# Control_and_gauge.net
KiCad netlist of a schematic drawn in Altium Designer
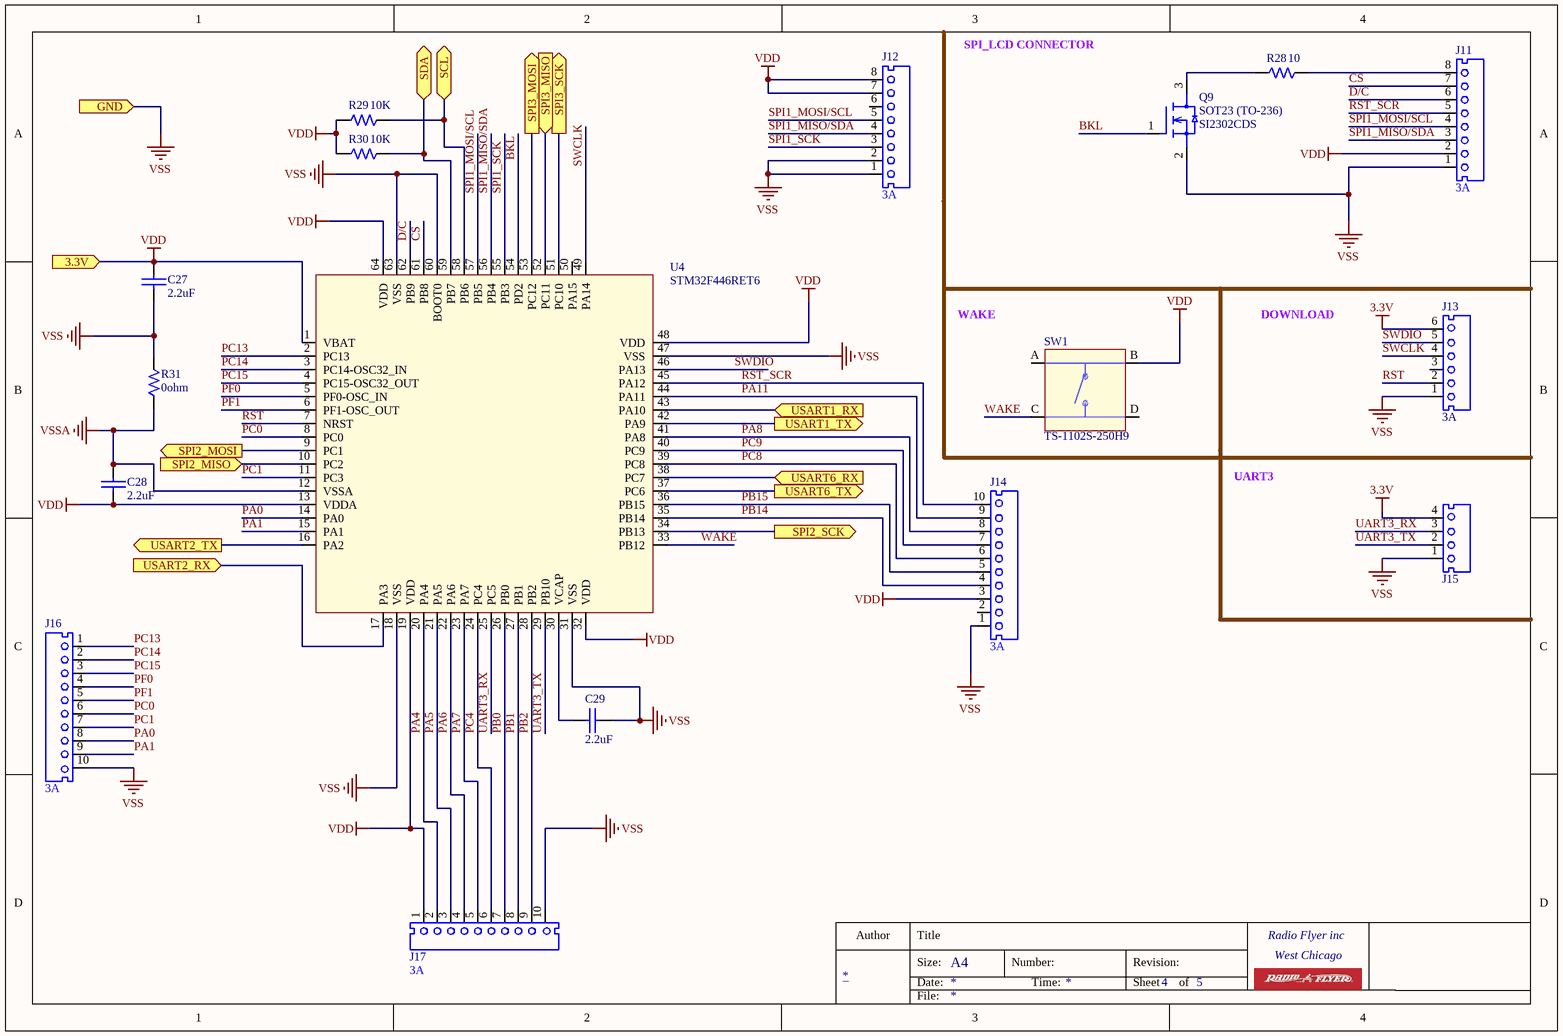
[diagram p0: Control and gauge.SchDoc]

(export (version "E")
  (design (tool "Eeschema 10.0.6"))
  (components
    (comp (ref "C27")
      (value "2.2uF")
      (footprint "CAPC0603-RW")
      (description "CAP X7R .01UF 16V +-10% 0603 WALSIN L")
      (fields
        (field (name "MFG") "WALSIN")
        (field (name "TOLERANCE") "10%")
        (field (name "CREATE_NAME") "Nathan")
      )
      (libsource (lib "P-Capacitors") (part "CAP0603 0.01uF 16V 10%_X7R_WALSIN"))
    )
    (comp (ref "C28")
      (value "2.2uF")
      (footprint "CAPC0603-RW")
      (description "CAP X7R .01UF 16V +-10% 0603 WALSIN L")
      (fields
        (field (name "MFG") "WALSIN")
        (field (name "TOLERANCE") "10%")
        (field (name "CREATE_NAME") "Nathan")
      )
      (libsource (lib "P-Capacitors") (part "CAP0603 0.01uF 16V 10%_X7R_WALSIN"))
    )
    (comp (ref "C29")
      (value "2.2uF")
      (footprint "CAPC0603-RW")
      (description "CAP X7R .01UF 16V +-10% 0603 WALSIN L")
      (fields
        (field (name "MFG") "WALSIN")
        (field (name "TOLERANCE") "10%")
        (field (name "CREATE_NAME") "Nathan")
      )
      (libsource (lib "P-Capacitors") (part "CAP0603 0.01uF 16V 10%_X7R_WALSIN"))
    )
    (comp (ref "J11")
      (value "T690300135100")
      (footprint "CONN 8P PH=2.5 ST TJC3-8A-CS")
      (description "CONN 8PIN P2.5 M\\180 TJC3-8A-CS K")
      (fields
        (field (name "MFG") "JINJIA")
        (field (name "MFG PART") "TJC3-8A-CS")
        (field (name "CURRENT") "3A")
        (field (name "CREATE_NAME") "Nathan")
      )
      (libsource (lib "") (part "CONN 8P PH=2.5 ST TJC3-8A-CS_1"))
    )
    (comp (ref "J12")
      (value "T690300135100")
      (footprint "CONN 8P PH=2.5 ST TJC3-8A-CS")
      (description "CONN 8PIN P2.5 M\\180 TJC3-8A-CS K")
      (fields
        (field (name "MFG") "JINJIA")
        (field (name "MFG PART") "TJC3-8A-CS")
        (field (name "CURRENT") "3A")
        (field (name "CREATE_NAME") "Nathan")
      )
      (libsource (lib "C-Connector") (part "CONN 8P PH=2.5 ST TJC3-8A-CS"))
    )
    (comp (ref "J13")
      (value "CCN250000-0106")
      (footprint "CONN 6P PH=2.5mm B6B-XH-A")
      (description "GP CONNECTOR B6B-XH-A 6 PIN")
      (fields (field (name "CURRENT") "3A"))
      (libsource (lib "C-Connector") (part "CONN 6P PH=2.5mm B6B-XH-A"))
    )
    (comp (ref "J14")
      (value "T690300163300")
      (footprint "CONN 10P PH=2.5 ST TJC3-10A-CS")
      (description "CONN 10PIN P2.5 M\\180 TJC3-10A-CS K")
      (fields
        (field (name "MFG") "JINJIA")
        (field (name "MFG PART") "TJC3-10A-CS")
        (field (name "CURRENT") "3A")
        (field (name "CREATE_NAME") "Nathan")
      )
      (libsource (lib "C-Connector") (part "CONN 10P PH=2.5 ST TJC3-10A-CS"))
    )
    (comp (ref "J15")
      (value "T690300164400")
      (footprint "CONN 4P PH=2.5mm 440052-4")
      (description "GP CONNECTOR B4B-XH-A 4 PIN")
      (fields
        (field (name "MFG") "TE")
        (field (name "MFG PART") "440052-4")
        (field (name "CREATE_NAME") "Nathan")
      )
      (libsource (lib "C-Connector") (part "CONN 4P PH=2.5mm 440052-4_TE"))
    )
    (comp (ref "J16")
      (value "T690300163300")
      (footprint "CONN 10P PH=2.5 ST TJC3-10A-CS")
      (description "CONN 10PIN P2.5 M\\180 TJC3-10A-CS K")
      (fields
        (field (name "MFG") "JINJIA")
        (field (name "MFG PART") "TJC3-10A-CS")
        (field (name "CURRENT") "3A")
        (field (name "CREATE_NAME") "Nathan")
      )
      (libsource (lib "C-Connector") (part "CONN 10P PH=2.5 ST TJC3-10A-CS"))
    )
    (comp (ref "J17")
      (value "T690300163300")
      (footprint "CONN 10P PH=2.5 ST TJC3-10A-CS")
      (description "CONN 10PIN P2.5 M\\180 TJC3-10A-CS K")
      (fields
        (field (name "MFG") "JINJIA")
        (field (name "MFG PART") "TJC3-10A-CS")
        (field (name "CURRENT") "3A")
        (field (name "CREATE_NAME") "Nathan")
      )
      (libsource (lib "C-Connector") (part "CONN 10P PH=2.5 ST TJC3-10A-CS"))
    )
    (comp (ref "Q9")
      (value "SI2302CDS")
      (footprint "SOT23-132-RW")
      (description "NMOS FET-Si2302CDS")
      (fields
        (field (name "MFG") "VISHAY")
        (field (name "PACKAGE") "SOT23 (TO-236)")
        (field (name "MFG PART") "SI2302CDS")
        (field (name "CREATE_NAME") "Nathan")
      )
      (libsource (lib "R-Semiconductors") (part "SI2302CDS"))
    )
    (comp (ref "R28")
      (value "10")
      (footprint "0603-RW")
      (description "CHIP 976 OHM 100PPM +-1% 0603 WALS L")
      (fields (field (name "POWER") "0.1W") (field (name "MFG") "WALSIN") (field (name "CREATE_NAME") "Tom"))
      (libsource (lib "Q-Resistors") (part "RES0603 1/10W +-1% 976 OHM 100PPM"))
    )
    (comp (ref "R29")
      (value "10K")
      (footprint "0603-RW")
      (description "CHIP 976 OHM 100PPM +-1% 0603 WALS L")
      (fields (field (name "POWER") "0.1W") (field (name "MFG") "WALSIN") (field (name "CREATE_NAME") "Tom"))
      (libsource (lib "Q-Resistors") (part "RES0603 1/10W +-1% 976 OHM 100PPM"))
    )
    (comp (ref "R30")
      (value "10K")
      (footprint "0603-RW")
      (description "CHIP 976 OHM 100PPM +-1% 0603 WALS L")
      (fields (field (name "POWER") "0.1W") (field (name "MFG") "WALSIN") (field (name "CREATE_NAME") "Tom"))
      (libsource (lib "Q-Resistors") (part "RES0603 1/10W +-1% 976 OHM 100PPM"))
    )
    (comp (ref "R31")
      (value "0ohm")
      (footprint "0603-RW")
      (description "CHIP 976 OHM 100PPM +-1% 0603 WALS L")
      (fields (field (name "POWER") "0.1W") (field (name "MFG") "WALSIN") (field (name "CREATE_NAME") "Tom"))
      (libsource (lib "Q-Resistors") (part "RES0603 1/10W +-1% 976 OHM 100PPM"))
    )
    (comp (ref "SW1")
      (value "T670200014500")
      (footprint "TACT SW TS-1102S-250H9")
      (description "TACT SW TS-1102S-250H9 JINGJU K")
      (fields
        (field (name "MFG") "JINGJU")
        (field (name "VOLTAGE") "12V")
        (field (name "MFG PART") "TS-1102S-250H9")
        (field (name "CREATE_NAME") "Nathan")
      )
      (libsource (lib "M-Controls") (part "TACT SW TS-1102S-250H9"))
    )
    (comp (ref "U4")
      (value "T610300097225")
      (footprint "QFP50P1200X1200X160-64N")
      (description "MCU STM32F030RCT6TR LQFP64 ST K")
      (fields
        (field (name "MFG") "ST     (STM意法半導體)")
        (field (name "MFG PART") "STM32F446RET6")
        (field (name "CREATE_NAME") "Nathan")
      )
      (libsource (lib "R-Semiconductors") (part "STM32F030RCT6TR"))
    )
  )
  (nets
    (net (code "1") (name "/BKL") (class "Default")
      (node (ref "Q9") (pin "1") (pinfunction "G_1") (pintype "passive"))
      (node (ref "U4") (pin "54") (pinfunction "PD2_54") (pintype "passive"))
    )
    (net (code "2") (name "/CS") (class "Default")
      (node (ref "J11") (pin "7") (pinfunction "7_7") (pintype "passive"))
      (node (ref "U4") (pin "61") (pinfunction "PB8_61") (pintype "passive"))
    )
    (net (code "3") (name "/D{slash}C") (class "Default")
      (node (ref "J11") (pin "6") (pinfunction "6_6") (pintype "passive"))
      (node (ref "U4") (pin "62") (pinfunction "PB9_62") (pintype "passive"))
    )
    (net (code "4") (name "/PA0") (class "Default")
      (node (ref "J16") (pin "8") (pinfunction "8_8") (pintype "passive"))
      (node (ref "U4") (pin "14") (pinfunction "PA0_14") (pintype "passive"))
    )
    (net (code "5") (name "/PA1") (class "Default")
      (node (ref "J16") (pin "9") (pinfunction "9_9") (pintype "passive"))
      (node (ref "U4") (pin "15") (pinfunction "PA1_15") (pintype "passive"))
    )
    (net (code "6") (name "/PA4") (class "Default")
      (node (ref "J17") (pin "2") (pinfunction "2_2") (pintype "passive"))
      (node (ref "U4") (pin "20") (pinfunction "PA4_20") (pintype "passive"))
    )
    (net (code "7") (name "/PA5") (class "Default")
      (node (ref "J17") (pin "3") (pinfunction "3_3") (pintype "passive"))
      (node (ref "U4") (pin "21") (pinfunction "PA5_21") (pintype "passive"))
    )
    (net (code "8") (name "/PA6") (class "Default")
      (node (ref "J17") (pin "4") (pinfunction "4_4") (pintype "passive"))
      (node (ref "U4") (pin "22") (pinfunction "PA6_22") (pintype "passive"))
    )
    (net (code "9") (name "/PA7") (class "Default")
      (node (ref "J17") (pin "5") (pinfunction "5_5") (pintype "passive"))
      (node (ref "U4") (pin "23") (pinfunction "PA7_23") (pintype "passive"))
    )
    (net (code "10") (name "/PA8") (class "Default")
      (node (ref "J14") (pin "8") (pinfunction "8_8") (pintype "passive"))
      (node (ref "U4") (pin "41") (pinfunction "PA8_41") (pintype "passive"))
    )
    (net (code "11") (name "/PA11") (class "Default")
      (node (ref "J14") (pin "9") (pinfunction "9_9") (pintype "passive"))
      (node (ref "U4") (pin "44") (pinfunction "PA11_44") (pintype "passive"))
    )
    (net (code "12") (name "/PB0") (class "Default")
      (node (ref "J17") (pin "7") (pinfunction "7_7") (pintype "passive"))
      (node (ref "U4") (pin "26") (pinfunction "PB0_26") (pintype "passive"))
    )
    (net (code "13") (name "/PB1") (class "Default")
      (node (ref "J17") (pin "8") (pinfunction "8_8") (pintype "passive"))
      (node (ref "U4") (pin "27") (pinfunction "PB1_27") (pintype "passive"))
    )
    (net (code "14") (name "/PB2") (class "Default")
      (node (ref "J17") (pin "9") (pinfunction "9_9") (pintype "passive"))
      (node (ref "U4") (pin "28") (pinfunction "PB2_28") (pintype "passive"))
    )
    (net (code "15") (name "/PB14") (class "Default")
      (node (ref "J14") (pin "4") (pinfunction "4_4") (pintype "passive"))
      (node (ref "U4") (pin "35") (pinfunction "PB14_35") (pintype "passive"))
    )
    (net (code "16") (name "/PB15") (class "Default")
      (node (ref "J14") (pin "5") (pinfunction "5_5") (pintype "passive"))
      (node (ref "U4") (pin "36") (pinfunction "PB15_36") (pintype "passive"))
    )
    (net (code "17") (name "/PC0") (class "Default")
      (node (ref "J16") (pin "6") (pinfunction "6_6") (pintype "passive"))
      (node (ref "U4") (pin "8") (pinfunction "PC0_8") (pintype "passive"))
    )
    (net (code "18") (name "/PC1") (class "Default")
      (node (ref "J16") (pin "7") (pinfunction "7_7") (pintype "passive"))
      (node (ref "U4") (pin "11") (pinfunction "PC3_11") (pintype "passive"))
    )
    (net (code "19") (name "/PC4") (class "Default")
      (node (ref "J17") (pin "6") (pinfunction "6_6") (pintype "passive"))
      (node (ref "U4") (pin "24") (pinfunction "PC4_24") (pintype "passive"))
    )
    (net (code "20") (name "/PC8") (class "Default")
      (node (ref "J14") (pin "6") (pinfunction "6_6") (pintype "passive"))
      (node (ref "U4") (pin "39") (pinfunction "PC8_39") (pintype "passive"))
    )
    (net (code "21") (name "/PC9") (class "Default")
      (node (ref "J14") (pin "7") (pinfunction "7_7") (pintype "passive"))
      (node (ref "U4") (pin "40") (pinfunction "PC9_40") (pintype "passive"))
    )
    (net (code "22") (name "/PC13") (class "Default")
      (node (ref "J16") (pin "1") (pinfunction "1_1") (pintype "passive"))
      (node (ref "U4") (pin "2") (pinfunction "PC13_2") (pintype "passive"))
    )
    (net (code "23") (name "/PC14") (class "Default")
      (node (ref "J16") (pin "2") (pinfunction "2_2") (pintype "passive"))
      (node (ref "U4") (pin "3") (pinfunction "PC14-OSC32_IN_3") (pintype "passive"))
    )
    (net (code "24") (name "/PC15") (class "Default")
      (node (ref "J16") (pin "3") (pinfunction "3_3") (pintype "passive"))
      (node (ref "U4") (pin "4") (pinfunction "PC15-OSC32_OUT_4") (pintype "passive"))
    )
    (net (code "25") (name "/PF0") (class "Default")
      (node (ref "J16") (pin "4") (pinfunction "4_4") (pintype "passive"))
      (node (ref "U4") (pin "5") (pinfunction "PF0-OSC_IN_5") (pintype "passive"))
    )
    (net (code "26") (name "/PF1") (class "Default")
      (node (ref "J16") (pin "5") (pinfunction "5_5") (pintype "passive"))
      (node (ref "U4") (pin "6") (pinfunction "PF1-OSC_OUT_6") (pintype "passive"))
    )
    (net (code "27") (name "/RST") (class "Default")
      (node (ref "J13") (pin "2") (pinfunction "2_2") (pintype "passive"))
      (node (ref "U4") (pin "7") (pinfunction "NRST_7") (pintype "passive"))
    )
    (net (code "28") (name "/RST_SCR") (class "Default")
      (node (ref "J11") (pin "5") (pinfunction "5_5") (pintype "passive"))
      (node (ref "J14") (pin "10") (pinfunction "10_10") (pintype "passive"))
      (node (ref "U4") (pin "45") (pinfunction "PA12_45") (pintype "passive"))
    )
    (net (code "29") (name "/SCL") (class "Default")
      (node (ref "R29") (pin "2") (pinfunction "2_2") (pintype "passive"))
      (node (ref "U4") (pin "58") (pinfunction "PB6_58") (pintype "passive"))
    )
    (net (code "30") (name "/SDA") (class "Default")
      (node (ref "R30") (pin "2") (pinfunction "2_2") (pintype "passive"))
      (node (ref "U4") (pin "59") (pinfunction "PB7_59") (pintype "passive"))
    )
    (net (code "31") (name "/SPI1_MISO{slash}SDA") (class "Default")
      (node (ref "J11") (pin "3") (pinfunction "3_3") (pintype "passive"))
      (node (ref "J12") (pin "4") (pinfunction "4_4") (pintype "passive"))
      (node (ref "U4") (pin "56") (pinfunction "PB4_56") (pintype "passive"))
    )
    (net (code "32") (name "/SPI1_MOSI{slash}SCL") (class "Default")
      (node (ref "J11") (pin "4") (pinfunction "4_4") (pintype "passive"))
      (node (ref "J12") (pin "5") (pinfunction "5_5") (pintype "passive"))
      (node (ref "U4") (pin "57") (pinfunction "PB5_57") (pintype "passive"))
    )
    (net (code "33") (name "/SPI1_SCK") (class "Default")
      (node (ref "J12") (pin "3") (pinfunction "3_3") (pintype "passive"))
      (node (ref "U4") (pin "55") (pinfunction "PB3_55") (pintype "passive"))
    )
    (net (code "34") (name "/SPI2_MISO") (class "Default")
      (node (ref "U4") (pin "10") (pinfunction "PC2_10") (pintype "passive"))
    )
    (net (code "35") (name "/SPI2_MOSI") (class "Default")
      (node (ref "U4") (pin "9") (pinfunction "PC1_9") (pintype "passive"))
    )
    (net (code "36") (name "/SPI2_SCK") (class "Default")
      (node (ref "U4") (pin "34") (pinfunction "PB13_34") (pintype "passive"))
    )
    (net (code "37") (name "/SPI3_MISO") (class "Default")
      (node (ref "U4") (pin "52") (pinfunction "PC11_52") (pintype "passive"))
    )
    (net (code "38") (name "/SPI3_MOSI") (class "Default")
      (node (ref "U4") (pin "53") (pinfunction "PC12_53") (pintype "passive"))
    )
    (net (code "39") (name "/SPI3_SCK") (class "Default")
      (node (ref "U4") (pin "51") (pinfunction "PC10_51") (pintype "passive"))
    )
    (net (code "40") (name "/SWCLK") (class "Default")
      (node (ref "J13") (pin "4") (pinfunction "4_4") (pintype "passive"))
      (node (ref "U4") (pin "49") (pinfunction "PA14_49") (pintype "passive"))
    )
    (net (code "41") (name "/SWDIO") (class "Default")
      (node (ref "J13") (pin "5") (pinfunction "5_5") (pintype "passive"))
      (node (ref "U4") (pin "46") (pinfunction "PA13_46") (pintype "passive"))
    )
    (net (code "42") (name "/UART3_RX") (class "Default")
      (node (ref "J15") (pin "3") (pinfunction "3_3") (pintype "passive"))
      (node (ref "U4") (pin "25") (pinfunction "PC5_25") (pintype "passive"))
    )
    (net (code "43") (name "/UART3_TX") (class "Default")
      (node (ref "J15") (pin "2") (pinfunction "2_2") (pintype "passive"))
      (node (ref "U4") (pin "29") (pinfunction "PB10_29") (pintype "passive"))
    )
    (net (code "44") (name "/USART1_RX") (class "Default")
      (node (ref "U4") (pin "43") (pinfunction "PA10_43") (pintype "passive"))
    )
    (net (code "45") (name "/USART1_TX") (class "Default")
      (node (ref "U4") (pin "42") (pinfunction "PA9_42") (pintype "passive"))
    )
    (net (code "46") (name "/USART2_RX") (class "Default")
      (node (ref "U4") (pin "17") (pinfunction "PA3_17") (pintype "passive"))
    )
    (net (code "47") (name "/USART2_TX") (class "Default")
      (node (ref "U4") (pin "16") (pinfunction "PA2_16") (pintype "passive"))
    )
    (net (code "48") (name "/USART6_RX") (class "Default")
      (node (ref "U4") (pin "38") (pinfunction "PC7_38") (pintype "passive"))
    )
    (net (code "49") (name "/USART6_TX") (class "Default")
      (node (ref "U4") (pin "37") (pinfunction "PC6_37") (pintype "passive"))
    )
    (net (code "50") (name "/WAKE") (class "Default")
      (node (ref "SW1") (pin "C") (pinfunction "C_C") (pintype "passive"))
      (node (ref "U4") (pin "33") (pinfunction "PB12_33") (pintype "passive"))
    )
    (net (code "51") (name "3.3V") (class "Default")
      (node (ref "C27") (pin "2") (pinfunction "2_2") (pintype "passive"))
      (node (ref "C28") (pin "1") (pinfunction "1_1") (pintype "passive"))
      (node (ref "J11") (pin "2") (pinfunction "2_2") (pintype "passive"))
      (node (ref "J12") (pin "7") (pinfunction "7_7") (pintype "passive"))
      (node (ref "J12") (pin "8") (pinfunction "8_8") (pintype "passive"))
      (node (ref "J13") (pin "6") (pinfunction "6_6") (pintype "passive"))
      (node (ref "J14") (pin "3") (pinfunction "3_3") (pintype "passive"))
      (node (ref "J15") (pin "4") (pinfunction "4_4") (pintype "passive"))
      (node (ref "J17") (pin "1") (pinfunction "1_1") (pintype "passive"))
      (node (ref "R29") (pin "1") (pinfunction "1_1") (pintype "passive"))
      (node (ref "R30") (pin "1") (pinfunction "1_1") (pintype "passive"))
      (node (ref "SW1") (pin "B") (pinfunction "B_B") (pintype "passive"))
      (node (ref "U4") (pin "1") (pinfunction "VBAT_1") (pintype "passive"))
      (node (ref "U4") (pin "13") (pinfunction "VDDA_13") (pintype "passive"))
      (node (ref "U4") (pin "19") (pinfunction "VDD_19") (pintype "passive"))
      (node (ref "U4") (pin "32") (pinfunction "VDD_32") (pintype "passive"))
      (node (ref "U4") (pin "48") (pinfunction "VDD_48") (pintype "passive"))
      (node (ref "U4") (pin "64") (pinfunction "VDD_64") (pintype "passive"))
    )
    (net (code "52") (name "Net-(J11-Pad8)") (class "Default")
      (node (ref "J11") (pin "8") (pinfunction "8_8") (pintype "passive"))
      (node (ref "R28") (pin "2") (pinfunction "2_2") (pintype "passive"))
    )
    (net (code "53") (name "Net-(Q9-D)") (class "Default")
      (node (ref "Q9") (pin "3") (pinfunction "D_3") (pintype "passive"))
      (node (ref "R28") (pin "1") (pinfunction "1_1") (pintype "passive"))
    )
    (net (code "54") (name "Net-(U4-VCAP)") (class "Default")
      (node (ref "C29") (pin "2") (pinfunction "2_2") (pintype "passive"))
      (node (ref "U4") (pin "30") (pinfunction "VCAP_30") (pintype "passive"))
    )
    (net (code "55") (name "VSS") (class "Default")
      (node (ref "C27") (pin "1") (pinfunction "1_1") (pintype "passive"))
      (node (ref "C29") (pin "1") (pinfunction "1_1") (pintype "passive"))
      (node (ref "J11") (pin "1") (pinfunction "1_1") (pintype "passive"))
      (node (ref "J12") (pin "1") (pinfunction "1_1") (pintype "passive"))
      (node (ref "J12") (pin "2") (pinfunction "2_2") (pintype "passive"))
      (node (ref "J13") (pin "1") (pinfunction "1_1") (pintype "passive"))
      (node (ref "J14") (pin "1") (pinfunction "1_1") (pintype "passive"))
      (node (ref "J15") (pin "1") (pinfunction "1_1") (pintype "passive"))
      (node (ref "J16") (pin "10") (pinfunction "10_10") (pintype "passive"))
      (node (ref "J17") (pin "10") (pinfunction "10_10") (pintype "passive"))
      (node (ref "Q9") (pin "2") (pinfunction "S_2") (pintype "passive"))
      (node (ref "R31") (pin "2") (pinfunction "2_2") (pintype "passive"))
      (node (ref "U4") (pin "18") (pinfunction "VSS_18") (pintype "passive"))
      (node (ref "U4") (pin "31") (pinfunction "VSS_31") (pintype "passive"))
      (node (ref "U4") (pin "47") (pinfunction "VSS_47") (pintype "passive"))
      (node (ref "U4") (pin "60") (pinfunction "BOOT0_60") (pintype "passive"))
      (node (ref "U4") (pin "63") (pinfunction "VSS_63") (pintype "passive"))
    )
    (net (code "56") (name "VSSA") (class "Default")
      (node (ref "C28") (pin "2") (pinfunction "2_2") (pintype "passive"))
      (node (ref "R31") (pin "1") (pinfunction "1_1") (pintype "passive"))
      (node (ref "U4") (pin "12") (pinfunction "VSSA_12") (pintype "passive"))
    )
    (net (code "57") (name "unconnected-(J12-Pad6)") (class "Default")
      (node (ref "J12") (pin "6") (pinfunction "6_6") (pintype "passive"))
    )
    (net (code "58") (name "unconnected-(J13-Pad3)") (class "Default")
      (node (ref "J13") (pin "3") (pinfunction "3_3") (pintype "passive"))
    )
    (net (code "59") (name "unconnected-(J14-Pad2)") (class "Default")
      (node (ref "J14") (pin "2") (pinfunction "2_2") (pintype "passive"))
    )
    (net (code "60") (name "unconnected-(SW1-PadA)") (class "Default")
      (node (ref "SW1") (pin "A") (pinfunction "A_A") (pintype "passive"))
    )
    (net (code "61") (name "unconnected-(SW1-PadD)") (class "Default")
      (node (ref "SW1") (pin "D") (pinfunction "D_D") (pintype "passive"))
    )
    (net (code "62") (name "unconnected-(U4-PA15-Pad50)") (class "Default")
      (node (ref "U4") (pin "50") (pinfunction "PA15_50") (pintype "passive"))
    )
  )
)
